# usb-midi-shield.net
KiCad netlist of a schematic drawn in EAGLE
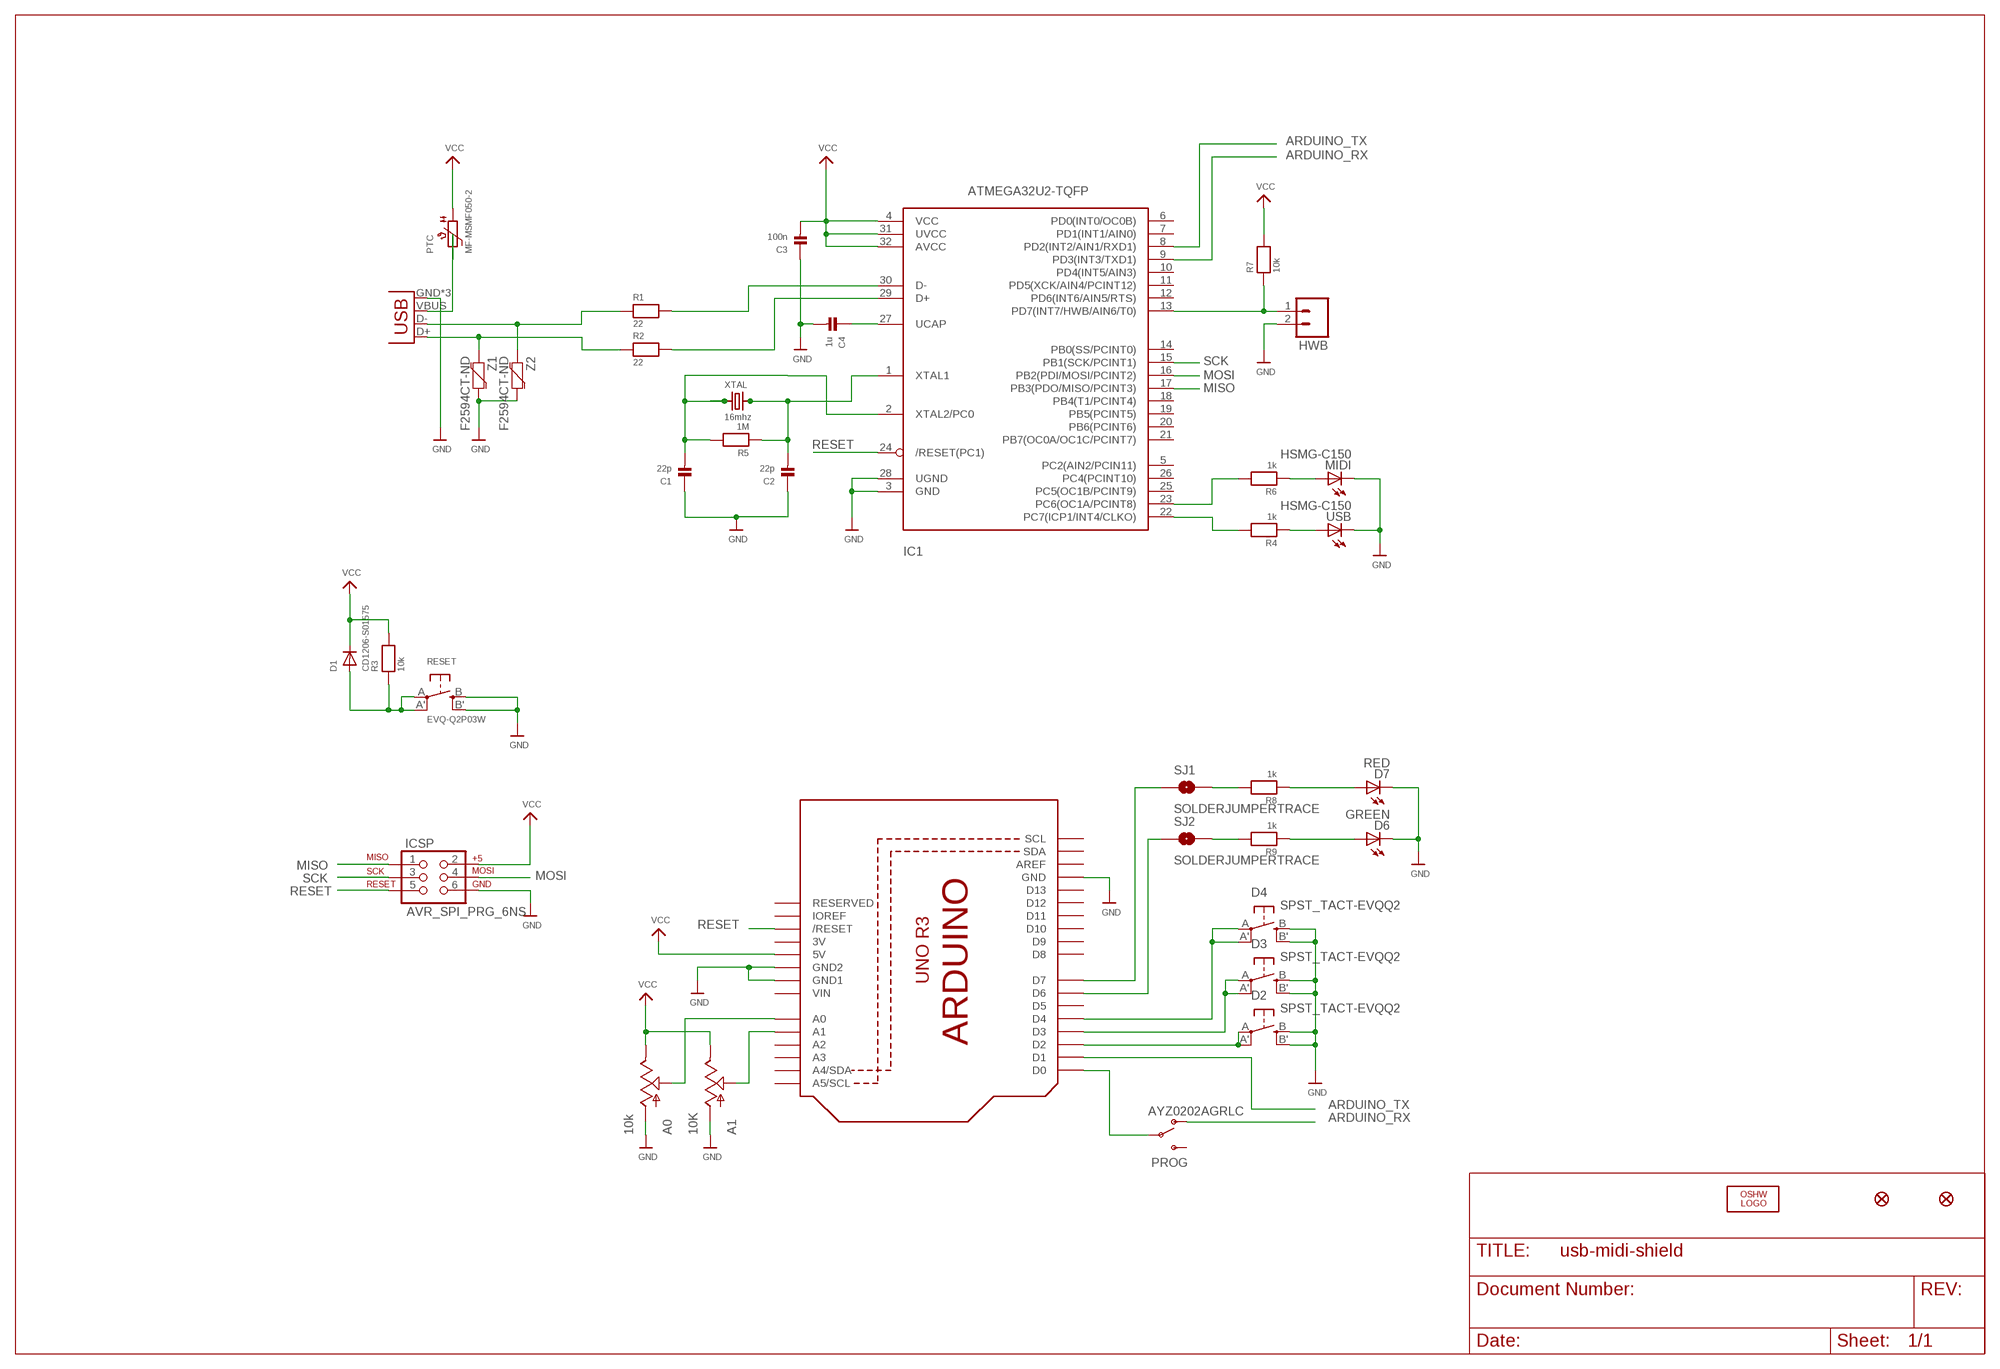
[diagram p0: schematic, sheet 1]

(export (version "E")
  (design (tool "Eeschema 10.0.6"))
  (components
    (comp (ref "A0")
      (value "10k")
      (footprint "eagle-import:ALPS_POT")
      (libsource (lib "eagle-import") (part "POT"))
    )
    (comp (ref "A1")
      (value "10K")
      (footprint "eagle-import:ALPS_POT")
      (libsource (lib "eagle-import") (part "POT"))
    )
    (comp (ref "C1")
      (value "22p")
      (footprint "eagle-import:0603")
      (libsource (lib "eagle-import") (part "CAP_CERAMIC0603"))
    )
    (comp (ref "C2")
      (value "22p")
      (footprint "eagle-import:0603")
      (libsource (lib "eagle-import") (part "CAP_CERAMIC0603"))
    )
    (comp (ref "C3")
      (value "100n")
      (footprint "eagle-import:0603")
      (libsource (lib "eagle-import") (part "CAP_CERAMIC0603"))
    )
    (comp (ref "C4")
      (value "1u")
      (footprint "eagle-import:0603")
      (libsource (lib "eagle-import") (part "CAP_CERAMIC0603"))
    )
    (comp (ref "D1")
      (value "CD1206-S01575")
      (footprint "eagle-import:SOD-123")
      (libsource (lib "eagle-import") (part "DIODESOD-123"))
    )
    (comp (ref "D2")
      (value "SPST_TACT-EVQQ2")
      (footprint "eagle-import:EVQ-Q2")
      (libsource (lib "eagle-import") (part "SPST_TACT-EVQQ2"))
    )
    (comp (ref "D3")
      (value "SPST_TACT-EVQQ2")
      (footprint "eagle-import:EVQ-Q2")
      (libsource (lib "eagle-import") (part "SPST_TACT-EVQQ2"))
    )
    (comp (ref "D4")
      (value "SPST_TACT-EVQQ2")
      (footprint "eagle-import:EVQ-Q2")
      (libsource (lib "eagle-import") (part "SPST_TACT-EVQQ2"))
    )
    (comp (ref "D6")
      (value "GREEN")
      (footprint "eagle-import:LED-1206")
      (fields (field (name "PROD_ID") "DIO-00862"))
      (libsource (lib "eagle-import") (part "LED-GREENLARGE"))
    )
    (comp (ref "D7")
      (value "RED")
      (footprint "eagle-import:LED-1206")
      (fields (field (name "PROD_ID") "DIO-00862"))
      (libsource (lib "eagle-import") (part "LED-GREENLARGE"))
    )
    (comp (ref "FID1")
      (value "FIDUCIAL1.5X3")
      (footprint "eagle-import:FIDUCIAL-1.5X3")
      (libsource (lib "eagle-import") (part "FIDUCIAL1.5X3"))
    )
    (comp (ref "FID2")
      (value "FIDUCIAL1.5X3")
      (footprint "eagle-import:FIDUCIAL-1.5X3")
      (libsource (lib "eagle-import") (part "FIDUCIAL1.5X3"))
    )
    (comp (ref "HWB")
      (value "M02LOCK")
      (footprint "eagle-import:1X02_LOCK")
      (libsource (lib "eagle-import") (part "M02LOCK"))
    )
    (comp (ref "IC1")
      (value "ATMEGA32U2-TQFP")
      (footprint "eagle-import:TQFP32-08")
      (libsource (lib "eagle-import") (part "ATMEGA32U2-TQFP"))
    )
    (comp (ref "ICSP")
      (value "AVR_SPI_PRG_6NS")
      (footprint "eagle-import:2X3-NS")
      (libsource (lib "eagle-import") (part "AVR_SPI_PRG_6NS"))
    )
    (comp (ref "JP1")
      (value "USB-MICROB")
      (footprint "eagle-import:USB-MICROB")
      (libsource (lib "eagle-import") (part "USB-MICROB"))
    )
    (comp (ref "LOGO1")
      (value "OSHW_LOGO_FILLX0350-NT")
      (footprint "eagle-import:OSHW_FILLX350_NOTEXT")
      (libsource (lib "eagle-import") (part "OSHW_LOGO_FILLX0350-NT"))
    )
    (comp (ref "MIDI")
      (value "HSMG-C150")
      (footprint "eagle-import:LED-1206")
      (libsource (lib "eagle-import") (part "LED-GREENLARGE"))
    )
    (comp (ref "PROG")
      (value "AYZ0202AGRLC")
      (footprint "eagle-import:AYZ0202")
      (libsource (lib "eagle-import") (part "SWITCH-SPDTSMD"))
    )
    (comp (ref "PTC")
      (value "MF-MSMF050-2")
      (footprint "eagle-import:PTC1812")
      (libsource (lib "eagle-import") (part "PTC1812"))
    )
    (comp (ref "R1")
      (value "22")
      (footprint "eagle-import:0805")
      (libsource (lib "eagle-import") (part "RESISTOR0805"))
    )
    (comp (ref "R2")
      (value "22")
      (footprint "eagle-import:0805")
      (libsource (lib "eagle-import") (part "RESISTOR0805"))
    )
    (comp (ref "R3")
      (value "10k")
      (footprint "eagle-import:0805")
      (libsource (lib "eagle-import") (part "RESISTOR0805"))
    )
    (comp (ref "R4")
      (value "1k")
      (footprint "eagle-import:0805")
      (libsource (lib "eagle-import") (part "RESISTOR0805"))
    )
    (comp (ref "R5")
      (value "1M")
      (footprint "eagle-import:0805")
      (libsource (lib "eagle-import") (part "RESISTOR0805"))
    )
    (comp (ref "R6")
      (value "1k")
      (footprint "eagle-import:0805")
      (libsource (lib "eagle-import") (part "RESISTOR0805"))
    )
    (comp (ref "R7")
      (value "10k")
      (footprint "eagle-import:0805")
      (libsource (lib "eagle-import") (part "RESISTOR0805"))
    )
    (comp (ref "R8")
      (value "1k")
      (footprint "eagle-import:0805")
      (libsource (lib "eagle-import") (part "RESISTOR0805"))
    )
    (comp (ref "R9")
      (value "1k")
      (footprint "eagle-import:0805")
      (libsource (lib "eagle-import") (part "RESISTOR0805"))
    )
    (comp (ref "RESET")
      (value "EVQ-Q2P03W")
      (footprint "eagle-import:EVQ-Q2")
      (libsource (lib "eagle-import") (part "SWITCH_TACT_SMT"))
    )
    (comp (ref "SJ1")
      (value "SOLDERJUMPERTRACE")
      (footprint "eagle-import:SJ_2S-TRACE")
      (libsource (lib "eagle-import") (part "SOLDERJUMPERTRACE"))
    )
    (comp (ref "SJ2")
      (value "SOLDERJUMPERTRACE")
      (footprint "eagle-import:SJ_2S-TRACE")
      (libsource (lib "eagle-import") (part "SOLDERJUMPERTRACE"))
    )
    (comp (ref "U1")
      (value "ARDUINOR3NODIM")
      (footprint "eagle-import:ARDUINOR3-NODIM")
      (libsource (lib "eagle-import") (part "ARDUINOR3NODIM"))
    )
    (comp (ref "USB")
      (value "HSMG-C150")
      (footprint "eagle-import:LED-1206")
      (libsource (lib "eagle-import") (part "LED-GREENLARGE"))
    )
    (comp (ref "XTAL")
      (value "16mhz")
      (footprint "eagle-import:HC49UP")
      (libsource (lib "eagle-import") (part "CRYSTALSMD"))
    )
    (comp (ref "Z1")
      (value "F2594CT-ND")
      (footprint "eagle-import:0603-RES")
      (libsource (lib "eagle-import") (part "VARISTOR-0603"))
    )
    (comp (ref "Z2")
      (value "F2594CT-ND")
      (footprint "eagle-import:0603-RES")
      (libsource (lib "eagle-import") (part "VARISTOR-0603"))
    )
  )
  (nets
    (net (code "1") (name "/3V") (class "Default")
      (node (ref "U1") (pin "3V") (pinfunction "3V_3V") (pintype "power_in"))
    )
    (net (code "2") (name "/ARDUINO_RX") (class "Default")
      (node (ref "IC1") (pin "9") (pinfunction "PD3(INT3/TXD1)_9") (pintype "bidirectional"))
      (node (ref "PROG") (pin "1") (pinfunction "O_1") (pintype "passive"))
    )
    (net (code "3") (name "/ARDUINO_TX") (class "Default")
      (node (ref "IC1") (pin "8") (pinfunction "PD2(INT2/AIN1/RXD1)_8") (pintype "bidirectional"))
      (node (ref "U1") (pin "D1") (pinfunction "D1_D1") (pintype "bidirectional"))
    )
    (net (code "4") (name "/MISO") (class "Default")
      (node (ref "IC1") (pin "17") (pinfunction "PB3(PDO/MISO/PCINT3)_17") (pintype "bidirectional"))
      (node (ref "ICSP") (pin "1") (pinfunction "1_1") (pintype "passive"))
    )
    (net (code "5") (name "/MOSI") (class "Default")
      (node (ref "IC1") (pin "16") (pinfunction "PB2(PDI/MOSI/PCINT2)_16") (pintype "bidirectional"))
      (node (ref "ICSP") (pin "4") (pinfunction "4_4") (pintype "passive"))
    )
    (net (code "6") (name "/RESET") (class "Default")
      (node (ref "D1") (pin "A") (pinfunction "A_A") (pintype "passive"))
      (node (ref "IC1") (pin "24") (pinfunction "/RESET(PC1)_24") (pintype "bidirectional"))
      (node (ref "ICSP") (pin "5") (pinfunction "5_5") (pintype "passive"))
      (node (ref "R3") (pin "1") (pinfunction "1_1") (pintype "passive"))
      (node (ref "RESET") (pin "A") (pinfunction "P_A") (pintype "passive"))
      (node (ref "RESET") (pin "A'") (pinfunction "P1_A'") (pintype "passive"))
      (node (ref "U1") (pin "RESET") (pinfunction "/RESET_RESET") (pintype "bidirectional"))
    )
    (net (code "7") (name "/SCK") (class "Default")
      (node (ref "IC1") (pin "15") (pinfunction "PB1(SCK/PCINT1)_15") (pintype "bidirectional"))
      (node (ref "ICSP") (pin "3") (pinfunction "3_3") (pintype "passive"))
    )
    (net (code "8") (name "/VIN") (class "Default")
      (node (ref "U1") (pin "VIN") (pinfunction "VIN_VIN") (pintype "power_in"))
    )
    (net (code "9") (name "GND") (class "Default")
      (node (ref "A0") (pin "P$3") (pinfunction "A_P$3") (pintype "passive"))
      (node (ref "A1") (pin "P$3") (pinfunction "A_P$3") (pintype "passive"))
      (node (ref "C1") (pin "1") (pinfunction "P$1_1") (pintype "passive"))
      (node (ref "C2") (pin "1") (pinfunction "P$1_1") (pintype "passive"))
      (node (ref "C3") (pin "1") (pinfunction "P$1_1") (pintype "passive"))
      (node (ref "C4") (pin "2") (pinfunction "P$2_2") (pintype "passive"))
      (node (ref "D2") (pin "B") (pinfunction "S_B") (pintype "passive"))
      (node (ref "D2") (pin "B'") (pinfunction "S1_B'") (pintype "passive"))
      (node (ref "D3") (pin "B") (pinfunction "S_B") (pintype "passive"))
      (node (ref "D3") (pin "B'") (pinfunction "S1_B'") (pintype "passive"))
      (node (ref "D4") (pin "B") (pinfunction "S_B") (pintype "passive"))
      (node (ref "D4") (pin "B'") (pinfunction "S1_B'") (pintype "passive"))
      (node (ref "D6") (pin "C") (pinfunction "C_C") (pintype "passive"))
      (node (ref "D7") (pin "C") (pinfunction "C_C") (pintype "passive"))
      (node (ref "HWB") (pin "2") (pinfunction "2_2") (pintype "passive"))
      (node (ref "IC1") (pin "28") (pinfunction "UGND_28") (pintype "bidirectional"))
      (node (ref "IC1") (pin "3") (pinfunction "GND_3") (pintype "bidirectional"))
      (node (ref "ICSP") (pin "6") (pinfunction "6_6") (pintype "passive"))
      (node (ref "JP1") (pin "GND") (pinfunction "GND_GND") (pintype "bidirectional"))
      (node (ref "JP1") (pin "MT1") (pinfunction "GND_MT1") (pintype "bidirectional"))
      (node (ref "JP1") (pin "MT2") (pinfunction "GND_MT2") (pintype "bidirectional"))
      (node (ref "MIDI") (pin "C") (pinfunction "C_C") (pintype "passive"))
      (node (ref "RESET") (pin "B") (pinfunction "S_B") (pintype "passive"))
      (node (ref "RESET") (pin "B'") (pinfunction "S1_B'") (pintype "passive"))
      (node (ref "U1") (pin "GND") (pinfunction "GND_GND") (pintype "power_in"))
      (node (ref "U1") (pin "GND1") (pinfunction "GND1_GND1") (pintype "power_in"))
      (node (ref "U1") (pin "GND2") (pinfunction "GND2_GND2") (pintype "power_in"))
      (node (ref "USB") (pin "C") (pinfunction "C_C") (pintype "passive"))
      (node (ref "Z1") (pin "2") (pinfunction "2_2") (pintype "passive"))
      (node (ref "Z2") (pin "2") (pinfunction "2_2") (pintype "passive"))
    )
    (net (code "10") (name "Net-(A0-S)") (class "Default")
      (node (ref "A0") (pin "P$2") (pinfunction "S_P$2") (pintype "passive"))
      (node (ref "U1") (pin "A0") (pinfunction "A0_A0") (pintype "bidirectional"))
    )
    (net (code "11") (name "Net-(A1-S)") (class "Default")
      (node (ref "A1") (pin "P$2") (pinfunction "S_P$2") (pintype "passive"))
      (node (ref "U1") (pin "A1") (pinfunction "A1_A1") (pintype "bidirectional"))
    )
    (net (code "12") (name "Net-(C1-P$2)") (class "Default")
      (node (ref "C1") (pin "2") (pinfunction "P$2_2") (pintype "passive"))
      (node (ref "IC1") (pin "2") (pinfunction "XTAL2/PC0_2") (pintype "bidirectional"))
      (node (ref "R5") (pin "2") (pinfunction "2_2") (pintype "passive"))
      (node (ref "XTAL") (pin "1") (pinfunction "1_1") (pintype "passive"))
    )
    (net (code "13") (name "Net-(C2-P$2)") (class "Default")
      (node (ref "C2") (pin "2") (pinfunction "P$2_2") (pintype "passive"))
      (node (ref "IC1") (pin "1") (pinfunction "XTAL1_1") (pintype "bidirectional"))
      (node (ref "R5") (pin "1") (pinfunction "1_1") (pintype "passive"))
      (node (ref "XTAL") (pin "2") (pinfunction "2_2") (pintype "passive"))
    )
    (net (code "14") (name "Net-(C4-P$1)") (class "Default")
      (node (ref "C4") (pin "1") (pinfunction "P$1_1") (pintype "passive"))
      (node (ref "IC1") (pin "27") (pinfunction "UCAP_27") (pintype "bidirectional"))
    )
    (net (code "15") (name "Net-(D2-P)") (class "Default")
      (node (ref "D2") (pin "A") (pinfunction "P_A") (pintype "passive"))
      (node (ref "D2") (pin "A'") (pinfunction "P1_A'") (pintype "passive"))
      (node (ref "U1") (pin "D2") (pinfunction "D2_D2") (pintype "bidirectional"))
    )
    (net (code "16") (name "Net-(D3-P)") (class "Default")
      (node (ref "D3") (pin "A") (pinfunction "P_A") (pintype "passive"))
      (node (ref "D3") (pin "A'") (pinfunction "P1_A'") (pintype "passive"))
      (node (ref "U1") (pin "D3") (pinfunction "D3_D3") (pintype "bidirectional"))
    )
    (net (code "17") (name "Net-(D4-P)") (class "Default")
      (node (ref "D4") (pin "A") (pinfunction "P_A") (pintype "passive"))
      (node (ref "D4") (pin "A'") (pinfunction "P1_A'") (pintype "passive"))
      (node (ref "U1") (pin "D4") (pinfunction "D4_D4") (pintype "bidirectional"))
    )
    (net (code "18") (name "Net-(D6-PadA)") (class "Default")
      (node (ref "D6") (pin "A") (pinfunction "A_A") (pintype "passive"))
      (node (ref "R9") (pin "1") (pinfunction "1_1") (pintype "passive"))
    )
    (net (code "19") (name "Net-(D7-PadA)") (class "Default")
      (node (ref "D7") (pin "A") (pinfunction "A_A") (pintype "passive"))
      (node (ref "R8") (pin "1") (pinfunction "1_1") (pintype "passive"))
    )
    (net (code "20") (name "Net-(IC1-D+)") (class "Default")
      (node (ref "IC1") (pin "29") (pinfunction "D+_29") (pintype "bidirectional"))
      (node (ref "R2") (pin "2") (pinfunction "2_2") (pintype "passive"))
    )
    (net (code "21") (name "Net-(IC1-D-)") (class "Default")
      (node (ref "IC1") (pin "30") (pinfunction "D-_30") (pintype "bidirectional"))
      (node (ref "R1") (pin "2") (pinfunction "2_2") (pintype "passive"))
    )
    (net (code "22") (name "Net-(IC1-PC6(OC1A{slash}PCINT8))") (class "Default")
      (node (ref "IC1") (pin "23") (pinfunction "PC6(OC1A/PCINT8)_23") (pintype "bidirectional"))
      (node (ref "R6") (pin "2") (pinfunction "2_2") (pintype "passive"))
    )
    (net (code "23") (name "Net-(IC1-PC7(ICP1{slash}INT4{slash}CLKO))") (class "Default")
      (node (ref "IC1") (pin "22") (pinfunction "PC7(ICP1/INT4/CLKO)_22") (pintype "bidirectional"))
      (node (ref "R4") (pin "2") (pinfunction "2_2") (pintype "passive"))
    )
    (net (code "24") (name "Net-(IC1-PD7(INT7{slash}HWB{slash}AIN6{slash}T0))") (class "Default")
      (node (ref "HWB") (pin "1") (pinfunction "1_1") (pintype "passive"))
      (node (ref "IC1") (pin "13") (pinfunction "PD7(INT7/HWB/AIN6/T0)_13") (pintype "bidirectional"))
      (node (ref "R7") (pin "1") (pinfunction "1_1") (pintype "passive"))
    )
    (net (code "25") (name "Net-(JP1-PadD+)") (class "Default")
      (node (ref "JP1") (pin "D+") (pinfunction "D+_D+") (pintype "bidirectional"))
      (node (ref "R2") (pin "1") (pinfunction "1_1") (pintype "passive"))
      (node (ref "Z1") (pin "1") (pinfunction "1_1") (pintype "passive"))
    )
    (net (code "26") (name "Net-(JP1-PadD-)") (class "Default")
      (node (ref "JP1") (pin "D-") (pinfunction "D-_D-") (pintype "bidirectional"))
      (node (ref "R1") (pin "1") (pinfunction "1_1") (pintype "passive"))
      (node (ref "Z2") (pin "1") (pinfunction "1_1") (pintype "passive"))
    )
    (net (code "27") (name "Net-(MIDI-PadA)") (class "Default")
      (node (ref "MIDI") (pin "A") (pinfunction "A_A") (pintype "passive"))
      (node (ref "R6") (pin "1") (pinfunction "1_1") (pintype "passive"))
    )
    (net (code "28") (name "Net-(PROG-P)") (class "Default")
      (node (ref "PROG") (pin "2") (pinfunction "P_2") (pintype "passive"))
      (node (ref "U1") (pin "D0") (pinfunction "D0_D0") (pintype "bidirectional"))
    )
    (net (code "29") (name "Net-(PTC-2)") (class "Default")
      (node (ref "JP1") (pin "VBUS") (pinfunction "VBUS_VBUS") (pintype "bidirectional"))
      (node (ref "PTC") (pin "P$2") (pinfunction "2_P$2") (pintype "passive"))
    )
    (net (code "30") (name "Net-(R4-Pad1)") (class "Default")
      (node (ref "R4") (pin "1") (pinfunction "1_1") (pintype "passive"))
      (node (ref "USB") (pin "A") (pinfunction "A_A") (pintype "passive"))
    )
    (net (code "31") (name "Net-(R8-Pad2)") (class "Default")
      (node (ref "R8") (pin "2") (pinfunction "2_2") (pintype "passive"))
      (node (ref "SJ1") (pin "2") (pinfunction "2_2") (pintype "passive"))
    )
    (net (code "32") (name "Net-(R9-Pad2)") (class "Default")
      (node (ref "R9") (pin "2") (pinfunction "2_2") (pintype "passive"))
      (node (ref "SJ2") (pin "2") (pinfunction "2_2") (pintype "passive"))
    )
    (net (code "33") (name "Net-(SJ1-Pad1)") (class "Default")
      (node (ref "SJ1") (pin "1") (pinfunction "1_1") (pintype "passive"))
      (node (ref "U1") (pin "D7") (pinfunction "D7_D7") (pintype "bidirectional"))
    )
    (net (code "34") (name "Net-(SJ2-Pad1)") (class "Default")
      (node (ref "SJ2") (pin "1") (pinfunction "1_1") (pintype "passive"))
      (node (ref "U1") (pin "D6") (pinfunction "D6_D6") (pintype "bidirectional"))
    )
    (net (code "35") (name "VCC") (class "Default")
      (node (ref "A0") (pin "P$1") (pinfunction "E_P$1") (pintype "passive"))
      (node (ref "A1") (pin "P$1") (pinfunction "E_P$1") (pintype "passive"))
      (node (ref "C3") (pin "2") (pinfunction "P$2_2") (pintype "passive"))
      (node (ref "D1") (pin "C") (pinfunction "C_C") (pintype "passive"))
      (node (ref "IC1") (pin "31") (pinfunction "UVCC_31") (pintype "bidirectional"))
      (node (ref "IC1") (pin "32") (pinfunction "AVCC_32") (pintype "bidirectional"))
      (node (ref "IC1") (pin "4") (pinfunction "VCC_4") (pintype "bidirectional"))
      (node (ref "ICSP") (pin "2") (pinfunction "2_2") (pintype "passive"))
      (node (ref "PTC") (pin "P$1") (pinfunction "1_P$1") (pintype "passive"))
      (node (ref "R3") (pin "2") (pinfunction "2_2") (pintype "passive"))
      (node (ref "R7") (pin "2") (pinfunction "2_2") (pintype "passive"))
      (node (ref "U1") (pin "5V") (pinfunction "5V_5V") (pintype "power_in"))
    )
    (net (code "36") (name "unconnected-(IC1-PB0(SS{slash}PCINT0)-Pad14)") (class "Default")
      (node (ref "IC1") (pin "14") (pinfunction "PB0(SS/PCINT0)_14") (pintype "bidirectional"))
    )
    (net (code "37") (name "unconnected-(IC1-PB4(T1{slash}PCINT4)-Pad18)") (class "Default")
      (node (ref "IC1") (pin "18") (pinfunction "PB4(T1/PCINT4)_18") (pintype "bidirectional"))
    )
    (net (code "38") (name "unconnected-(IC1-PB5(PCINT5)-Pad19)") (class "Default")
      (node (ref "IC1") (pin "19") (pinfunction "PB5(PCINT5)_19") (pintype "bidirectional"))
    )
    (net (code "39") (name "unconnected-(IC1-PB6(PCINT6)-Pad20)") (class "Default")
      (node (ref "IC1") (pin "20") (pinfunction "PB6(PCINT6)_20") (pintype "bidirectional"))
    )
    (net (code "40") (name "unconnected-(IC1-PB7(OC0A{slash}OC1C{slash}PCINT7)-Pad21)") (class "Default")
      (node (ref "IC1") (pin "21") (pinfunction "PB7(OC0A/OC1C/PCINT7)_21") (pintype "bidirectional"))
    )
    (net (code "41") (name "unconnected-(IC1-PC2(AIN2{slash}PCIN11)-Pad5)") (class "Default")
      (node (ref "IC1") (pin "5") (pinfunction "PC2(AIN2/PCIN11)_5") (pintype "bidirectional"))
    )
    (net (code "42") (name "unconnected-(IC1-PC4(PCINT10)-Pad26)") (class "Default")
      (node (ref "IC1") (pin "26") (pinfunction "PC4(PCINT10)_26") (pintype "bidirectional"))
    )
    (net (code "43") (name "unconnected-(IC1-PC5(OC1B{slash}PCINT9)-Pad25)") (class "Default")
      (node (ref "IC1") (pin "25") (pinfunction "PC5(OC1B/PCINT9)_25") (pintype "bidirectional"))
    )
    (net (code "44") (name "unconnected-(IC1-PD0(INT0{slash}OC0B)-Pad6)") (class "Default")
      (node (ref "IC1") (pin "6") (pinfunction "PD0(INT0/OC0B)_6") (pintype "bidirectional"))
    )
    (net (code "45") (name "unconnected-(IC1-PD1(INT1{slash}AIN0)-Pad7)") (class "Default")
      (node (ref "IC1") (pin "7") (pinfunction "PD1(INT1/AIN0)_7") (pintype "bidirectional"))
    )
    (net (code "46") (name "unconnected-(IC1-PD4(INT5{slash}AIN3)-Pad10)") (class "Default")
      (node (ref "IC1") (pin "10") (pinfunction "PD4(INT5/AIN3)_10") (pintype "bidirectional"))
    )
    (net (code "47") (name "unconnected-(IC1-PD5(XCK{slash}AIN4{slash}PCINT12)-Pad11)") (class "Default")
      (node (ref "IC1") (pin "11") (pinfunction "PD5(XCK/AIN4/PCINT12)_11") (pintype "bidirectional"))
    )
    (net (code "48") (name "unconnected-(IC1-PD6(INT6{slash}AIN5{slash}RTS)-Pad12)") (class "Default")
      (node (ref "IC1") (pin "12") (pinfunction "PD6(INT6/AIN5/RTS)_12") (pintype "bidirectional"))
    )
    (net (code "49") (name "unconnected-(PROG-S-Pad3)") (class "Default")
      (node (ref "PROG") (pin "3") (pinfunction "S_3") (pintype "passive"))
    )
    (net (code "50") (name "unconnected-(U1-A4{slash}SDA-PadA4)") (class "Default")
      (node (ref "U1") (pin "A4") (pinfunction "A4/SDA_A4") (pintype "bidirectional"))
    )
    (net (code "51") (name "unconnected-(U1-A5{slash}SCL-PadA5)") (class "Default")
      (node (ref "U1") (pin "A5") (pinfunction "A5/SCL_A5") (pintype "bidirectional"))
    )
    (net (code "52") (name "unconnected-(U1-PadA2)") (class "Default")
      (node (ref "U1") (pin "A2") (pinfunction "A2_A2") (pintype "bidirectional"))
    )
    (net (code "53") (name "unconnected-(U1-PadA3)") (class "Default")
      (node (ref "U1") (pin "A3") (pinfunction "A3_A3") (pintype "bidirectional"))
    )
    (net (code "54") (name "unconnected-(U1-PadAREF)") (class "Default")
      (node (ref "U1") (pin "AREF") (pinfunction "AREF_AREF") (pintype "bidirectional"))
    )
    (net (code "55") (name "unconnected-(U1-PadD5)") (class "Default")
      (node (ref "U1") (pin "D5") (pinfunction "D5_D5") (pintype "bidirectional"))
    )
    (net (code "56") (name "unconnected-(U1-PadD8)") (class "Default")
      (node (ref "U1") (pin "D8") (pinfunction "D8_D8") (pintype "bidirectional"))
    )
    (net (code "57") (name "unconnected-(U1-PadD9)") (class "Default")
      (node (ref "U1") (pin "D9") (pinfunction "D9_D9") (pintype "bidirectional"))
    )
    (net (code "58") (name "unconnected-(U1-PadD10)") (class "Default")
      (node (ref "U1") (pin "D10") (pinfunction "D10_D10") (pintype "bidirectional"))
    )
    (net (code "59") (name "unconnected-(U1-PadD11)") (class "Default")
      (node (ref "U1") (pin "D11") (pinfunction "D11_D11") (pintype "bidirectional"))
    )
    (net (code "60") (name "unconnected-(U1-PadD12)") (class "Default")
      (node (ref "U1") (pin "D12") (pinfunction "D12_D12") (pintype "bidirectional"))
    )
    (net (code "61") (name "unconnected-(U1-PadD13)") (class "Default")
      (node (ref "U1") (pin "D13") (pinfunction "D13_D13") (pintype "bidirectional"))
    )
    (net (code "62") (name "unconnected-(U1-PadIOREF)") (class "Default")
      (node (ref "U1") (pin "IOREF") (pinfunction "IOREF_IOREF") (pintype "output"))
    )
    (net (code "63") (name "unconnected-(U1-PadRESERVED)") (class "Default")
      (node (ref "U1") (pin "RESERVED") (pinfunction "RESERVED_RESERVED") (pintype "no_connect"))
    )
    (net (code "64") (name "unconnected-(U1-PadSCL)") (class "Default")
      (node (ref "U1") (pin "SCL") (pinfunction "SCL_SCL") (pintype "bidirectional"))
    )
    (net (code "65") (name "unconnected-(U1-PadSDA)") (class "Default")
      (node (ref "U1") (pin "SDA") (pinfunction "SDA_SDA") (pintype "bidirectional"))
    )
  )
)
